# CW308T_K24_Micro.net
KiCad netlist of a schematic drawn in Altium Designer
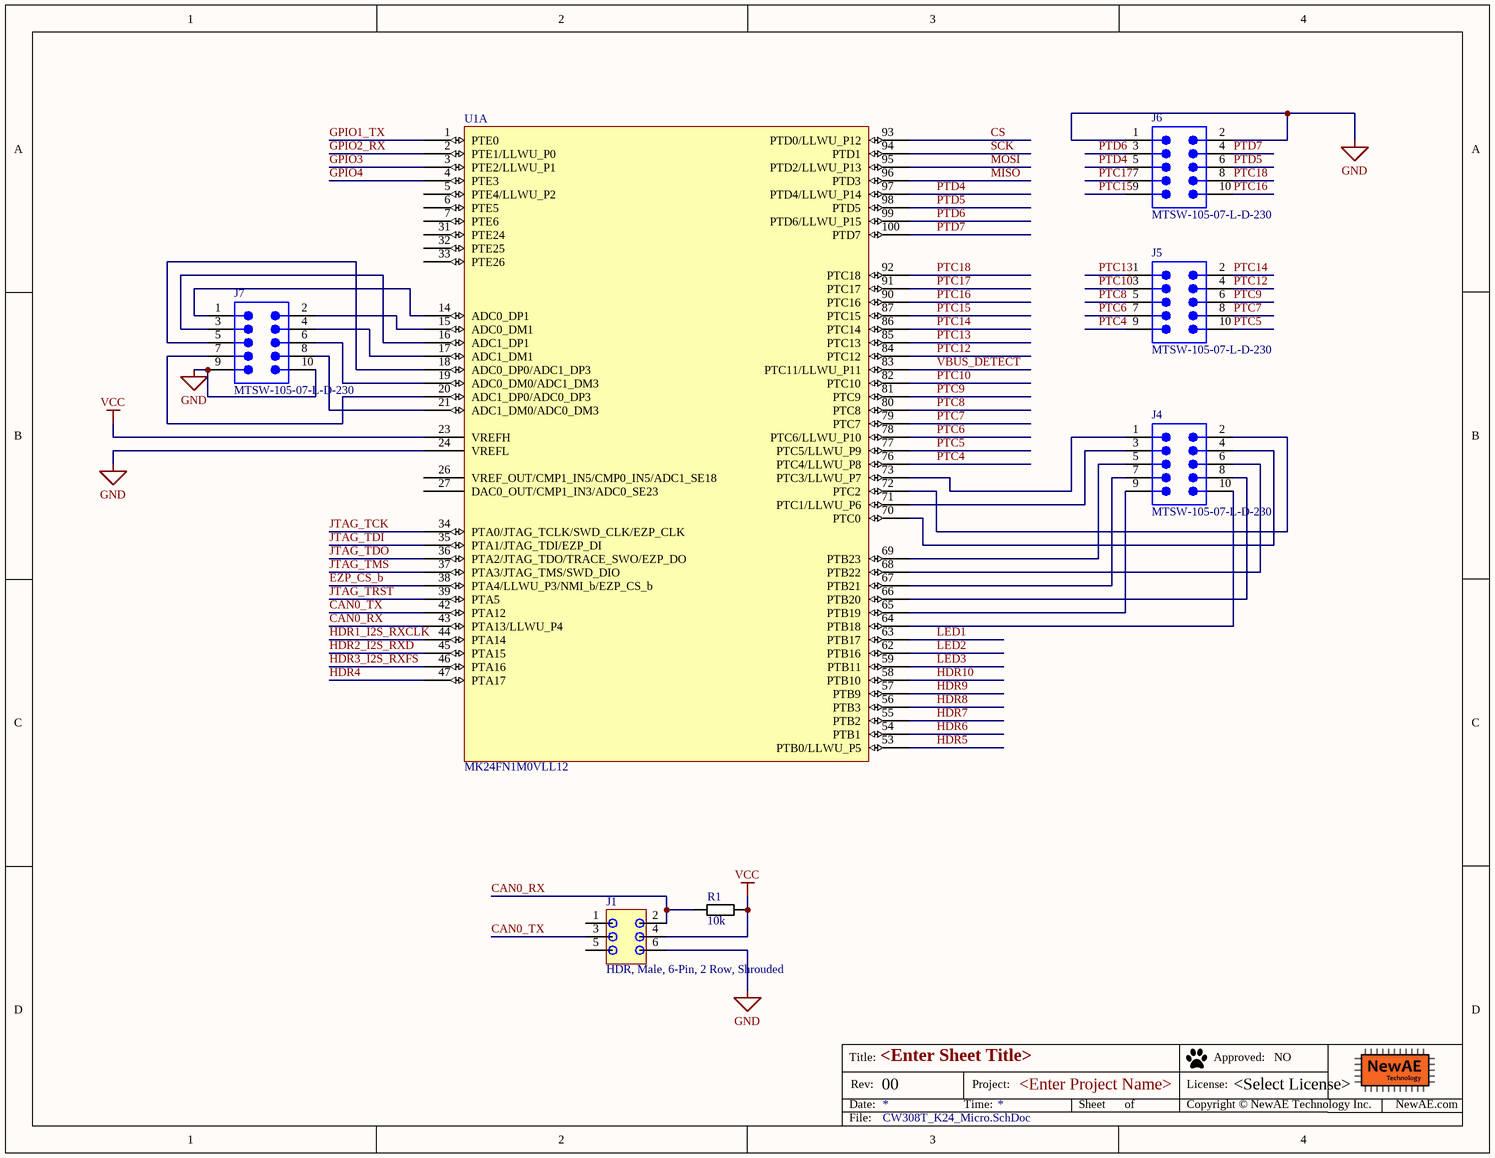
[diagram p0: CW308T_K24_Micro.SchDoc]

(export (version "E")
  (design (tool "Eeschema 10.0.6"))
  (components
    (comp (ref "J1")
      (value "HDR, Male, 6-Pin, 2 Row, Shrouded")
      (footprint "HDR_6PIN_2ROW_SHROUD")
      (fields (field (name "PART NUMBER") "HDR_6PIN_2ROW_SHROUD"))
      (libsource (lib "NewAE_AltiumLib") (part "CON6_2ROW"))
    )
    (comp (ref "J4")
      (value "MTSW-105-07-L-D-230")
      (footprint "SMTC-MTSW-105-07-X-D-230")
      (fields (field (name "MANUFACTURER") "Samtec"))
      (libsource (lib "Altium Content Vault") (part "SMTC-MTSW-105-X-X-D-X"))
    )
    (comp (ref "J5")
      (value "MTSW-105-07-L-D-230")
      (footprint "SMTC-MTSW-105-07-X-D-230")
      (fields (field (name "MANUFACTURER") "Samtec"))
      (libsource (lib "Altium Content Vault") (part "SMTC-MTSW-105-X-X-D-X"))
    )
    (comp (ref "J6")
      (value "MTSW-105-07-L-D-230")
      (footprint "SMTC-MTSW-105-07-X-D-230")
      (fields (field (name "MANUFACTURER") "Samtec"))
      (libsource (lib "Altium Content Vault") (part "SMTC-MTSW-105-X-X-D-X"))
    )
    (comp (ref "J7")
      (value "MTSW-105-07-L-D-230")
      (footprint "SMTC-MTSW-105-07-X-D-230")
      (fields (field (name "MANUFACTURER") "Samtec"))
      (libsource (lib "Altium Content Vault") (part "SMTC-MTSW-105-X-X-D-X"))
    )
    (comp (ref "R1")
      (value "10k")
      (footprint "RESC1608X55N")
      (description "10k res, 0603, 1%, 1/10W")
      (fields (field (name "PART NUMBER") "RCHIP-10K-0603") (field (name "TOLERANCE") "1%"))
      (libsource (lib "NewAE_AltiumLib") (part "RES-EU"))
    )
    (comp (ref "U1")
      (value "MK24FN1M0VLL12")
      (footprint "SQFP50P1600X1600X170-100N")
      (libsource (lib "NewAE_AltiumLib") (part "MK24FN1M0VLL12"))
    )
  )
  (nets
    (net (code "1") (name "/CAN0_RX") (class "Default")
      (node (ref "J1") (pin "2") (pinfunction "2_2") (pintype "passive"))
      (node (ref "R1") (pin "1") (pinfunction "1_1") (pintype "passive"))
      (node (ref "U1") (pin "43") (pinfunction "PTA13/LLWU_P4_43") (pintype "bidirectional"))
    )
    (net (code "2") (name "/CAN0_TX") (class "Default")
      (node (ref "J1") (pin "3") (pinfunction "3_3") (pintype "passive"))
      (node (ref "U1") (pin "42") (pinfunction "PTA12_42") (pintype "bidirectional"))
    )
    (net (code "3") (name "/CS") (class "Default")
      (node (ref "U1") (pin "93") (pinfunction "PTD0/LLWU_P12_93") (pintype "bidirectional"))
    )
    (net (code "4") (name "/EZP_CS_b") (class "Default")
      (node (ref "U1") (pin "38") (pinfunction "PTA4/LLWU_P3/NMI_b/EZP_CS_b_38") (pintype "bidirectional"))
    )
    (net (code "5") (name "/GPIO1_TX") (class "Default")
      (node (ref "U1") (pin "1") (pinfunction "PTE0_1") (pintype "bidirectional"))
    )
    (net (code "6") (name "/GPIO2_RX") (class "Default")
      (node (ref "U1") (pin "2") (pinfunction "PTE1/LLWU_P0_2") (pintype "bidirectional"))
    )
    (net (code "7") (name "/GPIO3") (class "Default")
      (node (ref "U1") (pin "3") (pinfunction "PTE2/LLWU_P1_3") (pintype "bidirectional"))
    )
    (net (code "8") (name "/GPIO4") (class "Default")
      (node (ref "U1") (pin "4") (pinfunction "PTE3_4") (pintype "bidirectional"))
    )
    (net (code "9") (name "/HDR1_I2S_RXCLK") (class "Default")
      (node (ref "U1") (pin "44") (pinfunction "PTA14_44") (pintype "bidirectional"))
    )
    (net (code "10") (name "/HDR2_I2S_RXD") (class "Default")
      (node (ref "U1") (pin "45") (pinfunction "PTA15_45") (pintype "bidirectional"))
    )
    (net (code "11") (name "/HDR3_I2S_RXFS") (class "Default")
      (node (ref "U1") (pin "46") (pinfunction "PTA16_46") (pintype "bidirectional"))
    )
    (net (code "12") (name "/HDR4") (class "Default")
      (node (ref "U1") (pin "47") (pinfunction "PTA17_47") (pintype "bidirectional"))
    )
    (net (code "13") (name "/HDR5") (class "Default")
      (node (ref "U1") (pin "53") (pinfunction "PTB0/LLWU_P5_53") (pintype "bidirectional"))
    )
    (net (code "14") (name "/HDR6") (class "Default")
      (node (ref "U1") (pin "54") (pinfunction "PTB1_54") (pintype "bidirectional"))
    )
    (net (code "15") (name "/HDR7") (class "Default")
      (node (ref "U1") (pin "55") (pinfunction "PTB2_55") (pintype "bidirectional"))
    )
    (net (code "16") (name "/HDR8") (class "Default")
      (node (ref "U1") (pin "56") (pinfunction "PTB3_56") (pintype "bidirectional"))
    )
    (net (code "17") (name "/HDR9") (class "Default")
      (node (ref "U1") (pin "57") (pinfunction "PTB9_57") (pintype "bidirectional"))
    )
    (net (code "18") (name "/HDR10") (class "Default")
      (node (ref "U1") (pin "58") (pinfunction "PTB10_58") (pintype "bidirectional"))
    )
    (net (code "19") (name "/JTAG_TCK") (class "Default")
      (node (ref "U1") (pin "34") (pinfunction "PTA0/JTAG_TCLK/SWD_CLK/EZP_CLK_34") (pintype "bidirectional"))
    )
    (net (code "20") (name "/JTAG_TDI") (class "Default")
      (node (ref "U1") (pin "35") (pinfunction "PTA1/JTAG_TDI/EZP_DI_35") (pintype "bidirectional"))
    )
    (net (code "21") (name "/JTAG_TDO") (class "Default")
      (node (ref "U1") (pin "36") (pinfunction "PTA2/JTAG_TDO/TRACE_SWO/EZP_DO_36") (pintype "bidirectional"))
    )
    (net (code "22") (name "/JTAG_TMS") (class "Default")
      (node (ref "U1") (pin "37") (pinfunction "PTA3/JTAG_TMS/SWD_DIO_37") (pintype "bidirectional"))
    )
    (net (code "23") (name "/JTAG_TRST") (class "Default")
      (node (ref "U1") (pin "39") (pinfunction "PTA5_39") (pintype "bidirectional"))
    )
    (net (code "24") (name "/LED1") (class "Default")
      (node (ref "U1") (pin "63") (pinfunction "PTB17_63") (pintype "bidirectional"))
    )
    (net (code "25") (name "/LED2") (class "Default")
      (node (ref "U1") (pin "62") (pinfunction "PTB16_62") (pintype "bidirectional"))
    )
    (net (code "26") (name "/LED3") (class "Default")
      (node (ref "U1") (pin "59") (pinfunction "PTB11_59") (pintype "bidirectional"))
    )
    (net (code "27") (name "/MISO") (class "Default")
      (node (ref "U1") (pin "96") (pinfunction "PTD3_96") (pintype "bidirectional"))
    )
    (net (code "28") (name "/MOSI") (class "Default")
      (node (ref "U1") (pin "95") (pinfunction "PTD2/LLWU_P13_95") (pintype "bidirectional"))
    )
    (net (code "29") (name "/PTC4") (class "Default")
      (node (ref "J5") (pin "9") (pinfunction "9_9") (pintype "passive"))
      (node (ref "U1") (pin "76") (pinfunction "PTC4/LLWU_P8_76") (pintype "bidirectional"))
    )
    (net (code "30") (name "/PTC5") (class "Default")
      (node (ref "J5") (pin "10") (pinfunction "10_10") (pintype "passive"))
      (node (ref "U1") (pin "77") (pinfunction "PTC5/LLWU_P9_77") (pintype "bidirectional"))
    )
    (net (code "31") (name "/PTC6") (class "Default")
      (node (ref "J5") (pin "7") (pinfunction "7_7") (pintype "passive"))
      (node (ref "U1") (pin "78") (pinfunction "PTC6/LLWU_P10_78") (pintype "bidirectional"))
    )
    (net (code "32") (name "/PTC7") (class "Default")
      (node (ref "J5") (pin "8") (pinfunction "8_8") (pintype "passive"))
      (node (ref "U1") (pin "79") (pinfunction "PTC7_79") (pintype "bidirectional"))
    )
    (net (code "33") (name "/PTC8") (class "Default")
      (node (ref "J5") (pin "5") (pinfunction "5_5") (pintype "passive"))
      (node (ref "U1") (pin "80") (pinfunction "PTC8_80") (pintype "bidirectional"))
    )
    (net (code "34") (name "/PTC9") (class "Default")
      (node (ref "J5") (pin "6") (pinfunction "6_6") (pintype "passive"))
      (node (ref "U1") (pin "81") (pinfunction "PTC9_81") (pintype "bidirectional"))
    )
    (net (code "35") (name "/PTC10") (class "Default")
      (node (ref "J5") (pin "3") (pinfunction "3_3") (pintype "passive"))
      (node (ref "U1") (pin "82") (pinfunction "PTC10_82") (pintype "bidirectional"))
    )
    (net (code "36") (name "/PTC12") (class "Default")
      (node (ref "J5") (pin "4") (pinfunction "4_4") (pintype "passive"))
      (node (ref "U1") (pin "84") (pinfunction "PTC12_84") (pintype "bidirectional"))
    )
    (net (code "37") (name "/PTC13") (class "Default")
      (node (ref "J5") (pin "1") (pinfunction "1_1") (pintype "passive"))
      (node (ref "U1") (pin "85") (pinfunction "PTC13_85") (pintype "bidirectional"))
    )
    (net (code "38") (name "/PTC14") (class "Default")
      (node (ref "J5") (pin "2") (pinfunction "2_2") (pintype "passive"))
      (node (ref "U1") (pin "86") (pinfunction "PTC14_86") (pintype "bidirectional"))
    )
    (net (code "39") (name "/PTC15") (class "Default")
      (node (ref "J6") (pin "9") (pinfunction "9_9") (pintype "passive"))
      (node (ref "U1") (pin "87") (pinfunction "PTC15_87") (pintype "bidirectional"))
    )
    (net (code "40") (name "/PTC16") (class "Default")
      (node (ref "J6") (pin "10") (pinfunction "10_10") (pintype "passive"))
      (node (ref "U1") (pin "90") (pinfunction "PTC16_90") (pintype "bidirectional"))
    )
    (net (code "41") (name "/PTC17") (class "Default")
      (node (ref "J6") (pin "7") (pinfunction "7_7") (pintype "passive"))
      (node (ref "U1") (pin "91") (pinfunction "PTC17_91") (pintype "bidirectional"))
    )
    (net (code "42") (name "/PTC18") (class "Default")
      (node (ref "J6") (pin "8") (pinfunction "8_8") (pintype "passive"))
      (node (ref "U1") (pin "92") (pinfunction "PTC18_92") (pintype "bidirectional"))
    )
    (net (code "43") (name "/PTD4") (class "Default")
      (node (ref "J6") (pin "5") (pinfunction "5_5") (pintype "passive"))
      (node (ref "U1") (pin "97") (pinfunction "PTD4/LLWU_P14_97") (pintype "bidirectional"))
    )
    (net (code "44") (name "/PTD5") (class "Default")
      (node (ref "J6") (pin "6") (pinfunction "6_6") (pintype "passive"))
      (node (ref "U1") (pin "98") (pinfunction "PTD5_98") (pintype "bidirectional"))
    )
    (net (code "45") (name "/PTD6") (class "Default")
      (node (ref "J6") (pin "3") (pinfunction "3_3") (pintype "passive"))
      (node (ref "U1") (pin "99") (pinfunction "PTD6/LLWU_P15_99") (pintype "bidirectional"))
    )
    (net (code "46") (name "/PTD7") (class "Default")
      (node (ref "J6") (pin "4") (pinfunction "4_4") (pintype "passive"))
      (node (ref "U1") (pin "100") (pinfunction "PTD7_100") (pintype "bidirectional"))
    )
    (net (code "47") (name "/SCK") (class "Default")
      (node (ref "U1") (pin "94") (pinfunction "PTD1_94") (pintype "bidirectional"))
    )
    (net (code "48") (name "/VBUS_DETECT") (class "Default")
      (node (ref "U1") (pin "83") (pinfunction "PTC11/LLWU_P11_83") (pintype "bidirectional"))
    )
    (net (code "49") (name "GND") (class "Default")
      (node (ref "J1") (pin "6") (pinfunction "6_6") (pintype "passive"))
      (node (ref "J6") (pin "1") (pinfunction "1_1") (pintype "passive"))
      (node (ref "J6") (pin "2") (pinfunction "2_2") (pintype "passive"))
      (node (ref "J7") (pin "10") (pinfunction "10_10") (pintype "passive"))
      (node (ref "J7") (pin "9") (pinfunction "9_9") (pintype "passive"))
      (node (ref "U1") (pin "24") (pinfunction "VREFL_24") (pintype "passive"))
    )
    (net (code "50") (name "Net-(U1A-ADC0_DM0{slash}ADC1_DM3)") (class "Default")
      (node (ref "J7") (pin "6") (pinfunction "6_6") (pintype "passive"))
      (node (ref "U1") (pin "19") (pinfunction "ADC0_DM0/ADC1_DM3_19") (pintype "bidirectional"))
    )
    (net (code "51") (name "Net-(U1A-ADC0_DM1)") (class "Default")
      (node (ref "J7") (pin "2") (pinfunction "2_2") (pintype "passive"))
      (node (ref "U1") (pin "15") (pinfunction "ADC0_DM1_15") (pintype "bidirectional"))
    )
    (net (code "52") (name "Net-(U1A-ADC0_DP0{slash}ADC1_DP3)") (class "Default")
      (node (ref "J7") (pin "5") (pinfunction "5_5") (pintype "passive"))
      (node (ref "U1") (pin "18") (pinfunction "ADC0_DP0/ADC1_DP3_18") (pintype "bidirectional"))
    )
    (net (code "53") (name "Net-(U1A-ADC0_DP1)") (class "Default")
      (node (ref "J7") (pin "1") (pinfunction "1_1") (pintype "passive"))
      (node (ref "U1") (pin "14") (pinfunction "ADC0_DP1_14") (pintype "bidirectional"))
    )
    (net (code "54") (name "Net-(U1A-ADC1_DM0{slash}ADC0_DM3)") (class "Default")
      (node (ref "J7") (pin "8") (pinfunction "8_8") (pintype "passive"))
      (node (ref "U1") (pin "21") (pinfunction "ADC1_DM0/ADC0_DM3_21") (pintype "bidirectional"))
    )
    (net (code "55") (name "Net-(U1A-ADC1_DM1)") (class "Default")
      (node (ref "J7") (pin "4") (pinfunction "4_4") (pintype "passive"))
      (node (ref "U1") (pin "17") (pinfunction "ADC1_DM1_17") (pintype "bidirectional"))
    )
    (net (code "56") (name "Net-(U1A-ADC1_DP0{slash}ADC0_DP3)") (class "Default")
      (node (ref "J7") (pin "7") (pinfunction "7_7") (pintype "passive"))
      (node (ref "U1") (pin "20") (pinfunction "ADC1_DP0/ADC0_DP3_20") (pintype "bidirectional"))
    )
    (net (code "57") (name "Net-(U1A-ADC1_DP1)") (class "Default")
      (node (ref "J7") (pin "3") (pinfunction "3_3") (pintype "passive"))
      (node (ref "U1") (pin "16") (pinfunction "ADC1_DP1_16") (pintype "bidirectional"))
    )
    (net (code "58") (name "Net-(U1A-PTB18)") (class "Default")
      (node (ref "J4") (pin "10") (pinfunction "10_10") (pintype "passive"))
      (node (ref "U1") (pin "64") (pinfunction "PTB18_64") (pintype "bidirectional"))
    )
    (net (code "59") (name "Net-(U1A-PTB19)") (class "Default")
      (node (ref "J4") (pin "9") (pinfunction "9_9") (pintype "passive"))
      (node (ref "U1") (pin "65") (pinfunction "PTB19_65") (pintype "bidirectional"))
    )
    (net (code "60") (name "Net-(U1A-PTB20)") (class "Default")
      (node (ref "J4") (pin "8") (pinfunction "8_8") (pintype "passive"))
      (node (ref "U1") (pin "66") (pinfunction "PTB20_66") (pintype "bidirectional"))
    )
    (net (code "61") (name "Net-(U1A-PTB21)") (class "Default")
      (node (ref "J4") (pin "7") (pinfunction "7_7") (pintype "passive"))
      (node (ref "U1") (pin "67") (pinfunction "PTB21_67") (pintype "bidirectional"))
    )
    (net (code "62") (name "Net-(U1A-PTB22)") (class "Default")
      (node (ref "J4") (pin "6") (pinfunction "6_6") (pintype "passive"))
      (node (ref "U1") (pin "68") (pinfunction "PTB22_68") (pintype "bidirectional"))
    )
    (net (code "63") (name "Net-(U1A-PTB23)") (class "Default")
      (node (ref "J4") (pin "5") (pinfunction "5_5") (pintype "passive"))
      (node (ref "U1") (pin "69") (pinfunction "PTB23_69") (pintype "bidirectional"))
    )
    (net (code "64") (name "Net-(U1A-PTC0)") (class "Default")
      (node (ref "J4") (pin "4") (pinfunction "4_4") (pintype "passive"))
      (node (ref "U1") (pin "70") (pinfunction "PTC0_70") (pintype "bidirectional"))
    )
    (net (code "65") (name "Net-(U1A-PTC1{slash}LLWU_P6)") (class "Default")
      (node (ref "J4") (pin "3") (pinfunction "3_3") (pintype "passive"))
      (node (ref "U1") (pin "71") (pinfunction "PTC1/LLWU_P6_71") (pintype "bidirectional"))
    )
    (net (code "66") (name "Net-(U1A-PTC2)") (class "Default")
      (node (ref "J4") (pin "2") (pinfunction "2_2") (pintype "passive"))
      (node (ref "U1") (pin "72") (pinfunction "PTC2_72") (pintype "bidirectional"))
    )
    (net (code "67") (name "Net-(U1A-PTC3{slash}LLWU_P7)") (class "Default")
      (node (ref "J4") (pin "1") (pinfunction "1_1") (pintype "passive"))
      (node (ref "U1") (pin "73") (pinfunction "PTC3/LLWU_P7_73") (pintype "bidirectional"))
    )
    (net (code "68") (name "VCC") (class "Default")
      (node (ref "J1") (pin "4") (pinfunction "4_4") (pintype "passive"))
      (node (ref "R1") (pin "2") (pinfunction "2_2") (pintype "passive"))
      (node (ref "U1") (pin "23") (pinfunction "VREFH_23") (pintype "passive"))
    )
    (net (code "69") (name "unconnected-(J1-Pad1)") (class "Default")
      (node (ref "J1") (pin "1") (pinfunction "1_1") (pintype "passive"))
    )
    (net (code "70") (name "unconnected-(J1-Pad5)") (class "Default")
      (node (ref "J1") (pin "5") (pinfunction "5_5") (pintype "passive"))
    )
    (net (code "71") (name "unconnected-(U1A-DAC0_OUT{slash}CMP1_IN3{slash}ADC0_SE23-Pad27)") (class "Default")
      (node (ref "U1") (pin "27") (pinfunction "DAC0_OUT/CMP1_IN3/ADC0_SE23_27") (pintype "passive"))
    )
    (net (code "72") (name "unconnected-(U1A-PTE4{slash}LLWU_P2-Pad5)") (class "Default")
      (node (ref "U1") (pin "5") (pinfunction "PTE4/LLWU_P2_5") (pintype "bidirectional"))
    )
    (net (code "73") (name "unconnected-(U1A-PTE5-Pad6)") (class "Default")
      (node (ref "U1") (pin "6") (pinfunction "PTE5_6") (pintype "bidirectional"))
    )
    (net (code "74") (name "unconnected-(U1A-PTE6-Pad7)") (class "Default")
      (node (ref "U1") (pin "7") (pinfunction "PTE6_7") (pintype "bidirectional"))
    )
    (net (code "75") (name "unconnected-(U1A-PTE24-Pad31)") (class "Default")
      (node (ref "U1") (pin "31") (pinfunction "PTE24_31") (pintype "bidirectional"))
    )
    (net (code "76") (name "unconnected-(U1A-PTE25-Pad32)") (class "Default")
      (node (ref "U1") (pin "32") (pinfunction "PTE25_32") (pintype "bidirectional"))
    )
    (net (code "77") (name "unconnected-(U1A-PTE26-Pad33)") (class "Default")
      (node (ref "U1") (pin "33") (pinfunction "PTE26_33") (pintype "bidirectional"))
    )
    (net (code "78") (name "unconnected-(U1A-VREF_OUT{slash}CMP1_IN5{slash}CMP0_IN5{slash}ADC1_SE18-Pad26)") (class "Default")
      (node (ref "U1") (pin "26") (pinfunction "VREF_OUT/CMP1_IN5/CMP0_IN5/ADC1_SE18_26") (pintype "passive"))
    )
  )
)
